# Proximity_sensor_v2.net
KiCad netlist of a schematic drawn in EAGLE
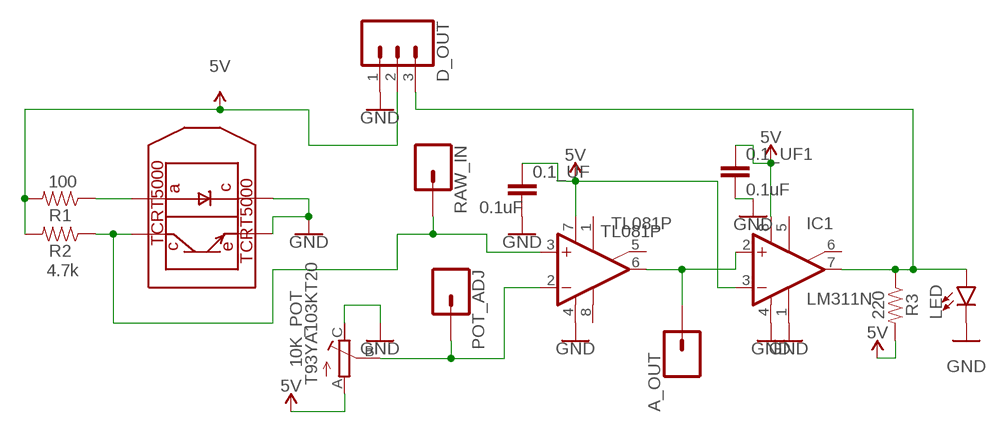
[diagram p0: schematic, sheet 1]

(export (version "E")
  (design (tool "Eeschema 10.0.6"))
  (components
    (comp (ref "0.1_UF")
      (value "0.1uF")
      (footprint "eagle-import:CAP-PTH-SMALL-KIT")
      (libsource (lib "eagle-import") (part "0.1UF-KIT-EZ-50V-20%"))
    )
    (comp (ref "0.1_UF1")
      (value "0.1uF")
      (footprint "eagle-import:CAP-PTH-SMALL-KIT")
      (libsource (lib "eagle-import") (part "0.1UF-KIT-EZ-50V-20%"))
    )
    (comp (ref "10K_POT")
      (value "T93YA103KT20")
      (footprint "eagle-import:TRIM_T93YA103KT20")
      (fields (field (name "DIGI-KEY_PART_NUMBER") "T93YA-10K-ND") (field (name "MF") "Vishay"))
      (libsource (lib "eagle-import") (part "T93YA103KT20"))
    )
    (comp (ref "A_OUT")
      (value "CONN_01")
      (footprint "eagle-import:1X01")
      (libsource (lib "eagle-import") (part "CONN_01"))
    )
    (comp (ref "D_OUT")
      (value "CONN_03")
      (footprint "eagle-import:1X03")
      (libsource (lib "eagle-import") (part "CONN_03"))
    )
    (comp (ref "IC1")
      (value "LM311N")
      (footprint "eagle-import:DIL08")
      (libsource (lib "eagle-import") (part "LM311N"))
    )
    (comp (ref "LED")
      (value "LED5MM")
      (footprint "eagle-import:LED_5MM")
      (libsource (lib "eagle-import") (part "LED5MM"))
    )
    (comp (ref "POT_ADJ")
      (value "CONN_01")
      (footprint "eagle-import:1X01")
      (libsource (lib "eagle-import") (part "CONN_01"))
    )
    (comp (ref "R1")
      (value "100")
      (footprint "eagle-import:AXIAL-0.3-KIT")
      (libsource (lib "eagle-import") (part "RESISTORAXIAL-0.3-KIT"))
    )
    (comp (ref "R2")
      (value "4.7k")
      (footprint "eagle-import:AXIAL-0.3-KIT")
      (libsource (lib "eagle-import") (part "RESISTORAXIAL-0.3-KIT"))
    )
    (comp (ref "R3")
      (value "220")
      (footprint "eagle-import:AXIAL-0.3-KIT")
      (libsource (lib "eagle-import") (part "RESISTORAXIAL-0.3-KIT"))
    )
    (comp (ref "RAW_IN")
      (value "CONN_01")
      (footprint "eagle-import:1X01")
      (libsource (lib "eagle-import") (part "CONN_01"))
    )
    (comp (ref "TCRT5000")
      (value "TCRT5000")
      (footprint "eagle-import:5000")
      (libsource (lib "eagle-import") (part "TCRT5000"))
    )
    (comp (ref "TL081P")
      (value "TL081P")
      (footprint "eagle-import:DIL08")
      (libsource (lib "eagle-import") (part "TL081P"))
    )
  )
  (nets
    (net (code "1") (name "5V") (class "Default")
      (node (ref "0.1_UF") (pin "1") (pinfunction "1_1") (pintype "passive"))
      (node (ref "0.1_UF1") (pin "1") (pinfunction "1_1") (pintype "passive"))
      (node (ref "10K_POT") (pin "A") (pinfunction "A_A") (pintype "passive"))
      (node (ref "D_OUT") (pin "2") (pinfunction "2_2") (pintype "passive"))
      (node (ref "IC1") (pin "3") (pinfunction "-IN_3") (pintype "input"))
      (node (ref "IC1") (pin "8") (pinfunction "V+_8") (pintype "power_in"))
      (node (ref "R1") (pin "P$2") (pinfunction "2_P$2") (pintype "passive"))
      (node (ref "R2") (pin "P$2") (pinfunction "2_P$2") (pintype "passive"))
      (node (ref "R3") (pin "P$2") (pinfunction "2_P$2") (pintype "passive"))
      (node (ref "TL081P") (pin "7") (pinfunction "V+_7") (pintype "power_in"))
    )
    (net (code "2") (name "GND") (class "Default")
      (node (ref "0.1_UF") (pin "2") (pinfunction "2_2") (pintype "passive"))
      (node (ref "0.1_UF1") (pin "2") (pinfunction "2_2") (pintype "passive"))
      (node (ref "10K_POT") (pin "C") (pinfunction "C_C") (pintype "passive"))
      (node (ref "D_OUT") (pin "1") (pinfunction "1_1") (pintype "passive"))
      (node (ref "IC1") (pin "1") (pinfunction "GND_1") (pintype "passive"))
      (node (ref "IC1") (pin "4") (pinfunction "V-_4") (pintype "power_in"))
      (node (ref "LED") (pin "K") (pinfunction "C_K") (pintype "passive"))
      (node (ref "TCRT5000") (pin "P$2") (pinfunction "P$2_P$2") (pintype "passive"))
      (node (ref "TCRT5000") (pin "P$4") (pinfunction "P$4_P$4") (pintype "passive"))
      (node (ref "TL081P") (pin "4") (pinfunction "V-_4") (pintype "power_in"))
    )
    (net (code "3") (name "Net-(IC1-+IN)") (class "Default")
      (node (ref "A_OUT") (pin "1") (pinfunction "1_1") (pintype "passive"))
      (node (ref "IC1") (pin "2") (pinfunction "+IN_2") (pintype "input"))
      (node (ref "TL081P") (pin "6") (pinfunction "OUT_6") (pintype "output"))
    )
    (net (code "4") (name "Net-(IC1-OUT)") (class "Default")
      (node (ref "D_OUT") (pin "3") (pinfunction "3_3") (pintype "passive"))
      (node (ref "IC1") (pin "7") (pinfunction "OUT_7") (pintype "output"))
      (node (ref "LED") (pin "A") (pinfunction "A_A") (pintype "passive"))
      (node (ref "R3") (pin "P$1") (pinfunction "1_P$1") (pintype "passive"))
    )
    (net (code "5") (name "Net-(R1-1)") (class "Default")
      (node (ref "R1") (pin "P$1") (pinfunction "1_P$1") (pintype "passive"))
      (node (ref "TCRT5000") (pin "P$3") (pinfunction "P$3_P$3") (pintype "passive"))
    )
    (net (code "6") (name "Net-(R2-1)") (class "Default")
      (node (ref "R2") (pin "P$1") (pinfunction "1_P$1") (pintype "passive"))
      (node (ref "RAW_IN") (pin "1") (pinfunction "1_1") (pintype "passive"))
      (node (ref "TCRT5000") (pin "P$1") (pinfunction "P$1_P$1") (pintype "passive"))
      (node (ref "TL081P") (pin "3") (pinfunction "+IN_3") (pintype "input"))
    )
    (net (code "7") (name "Net-(TL081P--IN)") (class "Default")
      (node (ref "10K_POT") (pin "B") (pinfunction "B_B") (pintype "passive"))
      (node (ref "POT_ADJ") (pin "1") (pinfunction "1_1") (pintype "passive"))
      (node (ref "TL081P") (pin "2") (pinfunction "-IN_2") (pintype "input"))
    )
    (net (code "8") (name "unconnected-(IC1-ON-Pad5)") (class "Default")
      (node (ref "IC1") (pin "5") (pinfunction "ON_5") (pintype "passive"))
    )
    (net (code "9") (name "unconnected-(IC1-ON{slash}STR-Pad6)") (class "Default")
      (node (ref "IC1") (pin "6") (pinfunction "ON/STR_6") (pintype "passive"))
    )
    (net (code "10") (name "unconnected-(TL081P-ON1-Pad1)") (class "Default")
      (node (ref "TL081P") (pin "1") (pinfunction "ON1_1") (pintype "passive"))
    )
    (net (code "11") (name "unconnected-(TL081P-ON2-Pad5)") (class "Default")
      (node (ref "TL081P") (pin "5") (pinfunction "ON2_5") (pintype "passive"))
    )
    (net (code "12") (name "unconnected-(TL081P-OPT-Pad8)") (class "Default")
      (node (ref "TL081P") (pin "8") (pinfunction "OPT_8") (pintype "passive"))
    )
  )
)
